# esquematico.net
KiCad netlist of a schematic drawn in EAGLE
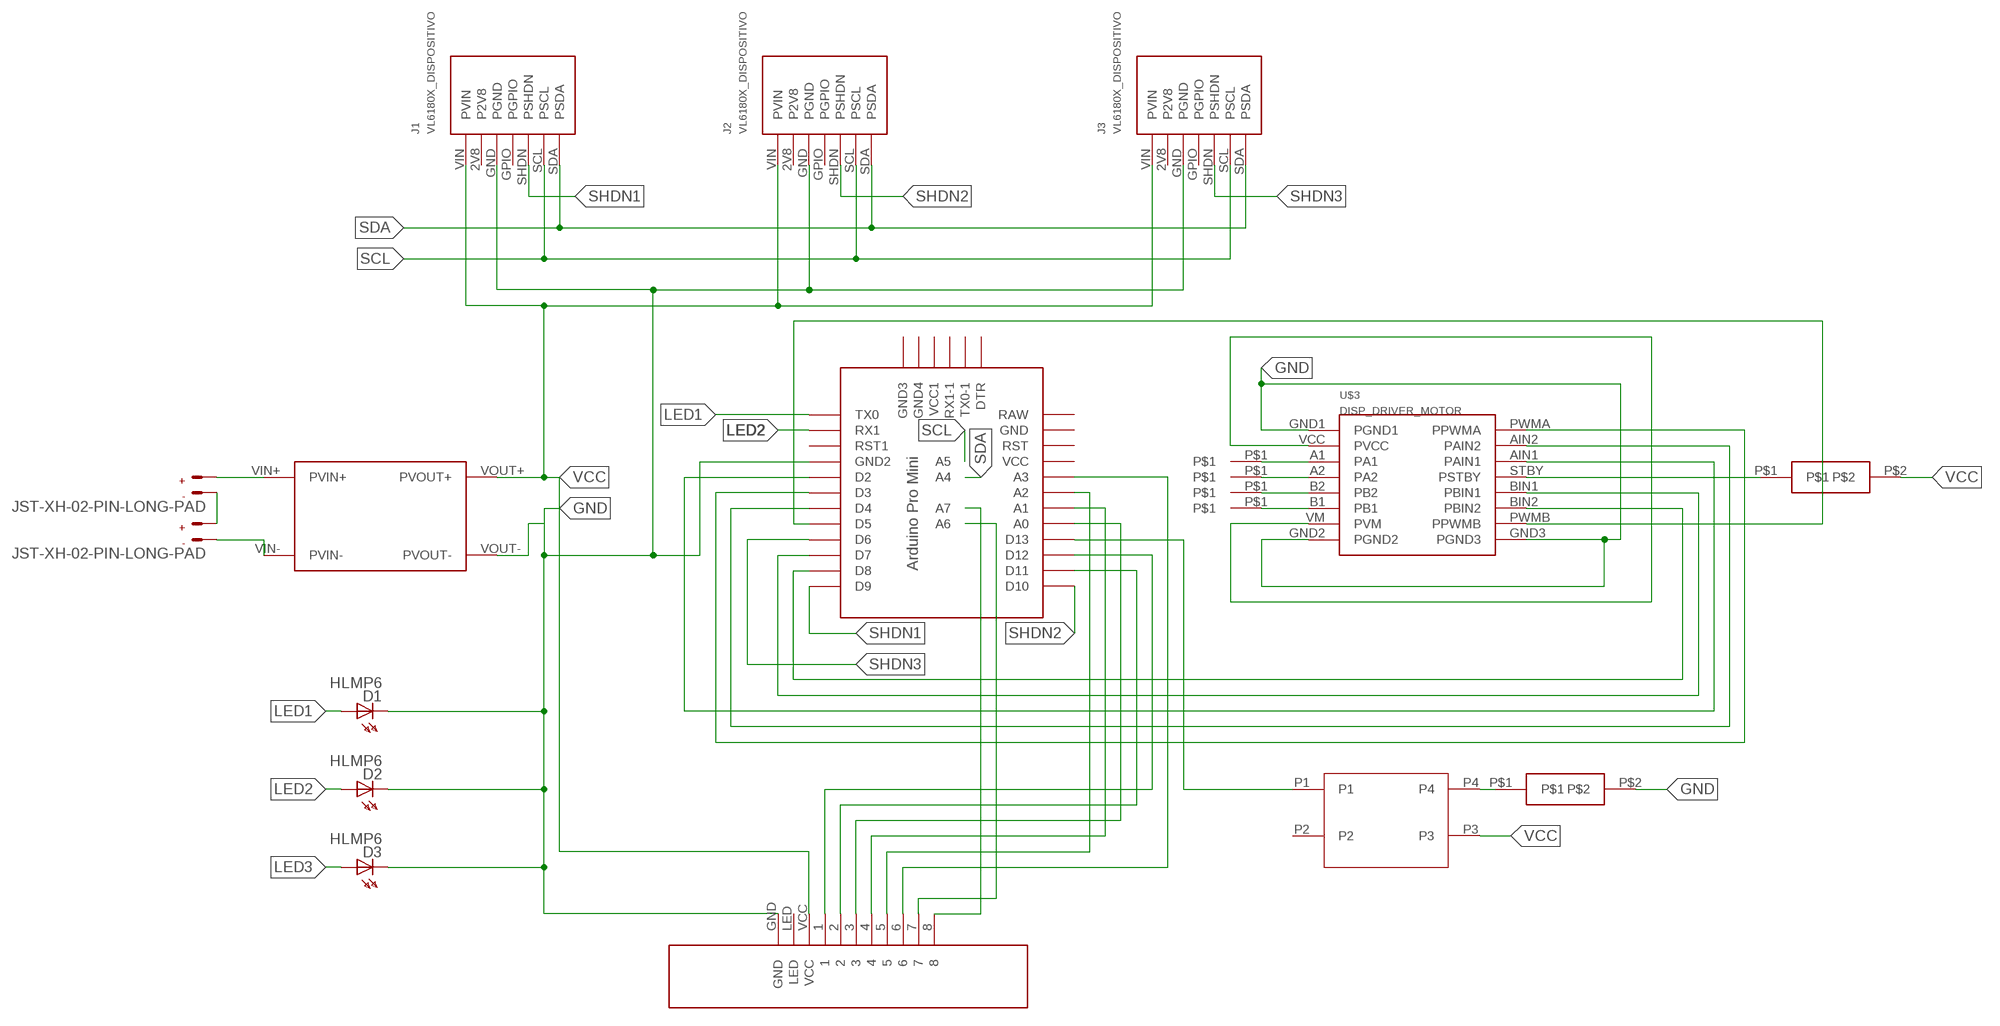
[diagram p0: schematic, sheet 1]

(export (version "E")
  (design (tool "Eeschema 10.0.6"))
  (components
    (comp (ref "D1")
      (value "HLMP6")
      (footprint "eagle-import:HLMP6")
      (fields (field (name "MF") "AGILENT TECHNOLOGIES") (field (name "MPN") "HLMP-6500"))
      (libsource (lib "eagle-import") (part "HLMP6"))
    )
    (comp (ref "D2")
      (value "HLMP6")
      (footprint "eagle-import:HLMP6")
      (fields (field (name "MF") "AGILENT TECHNOLOGIES") (field (name "MPN") "HLMP-6500"))
      (libsource (lib "eagle-import") (part "HLMP6"))
    )
    (comp (ref "D3")
      (value "HLMP6")
      (footprint "eagle-import:HLMP6")
      (fields (field (name "MF") "AGILENT TECHNOLOGIES") (field (name "MPN") "HLMP-6500"))
      (libsource (lib "eagle-import") (part "HLMP6"))
    )
    (comp (ref "DC1+")
      (value "PION_DVC")
      (footprint "eagle-import:PIN_PKG")
      (libsource (lib "eagle-import") (part "PION_DVC"))
    )
    (comp (ref "J1")
      (value "VL6180X_DISPOSITIVO")
      (footprint "eagle-import:VL6180X_PKG")
      (libsource (lib "eagle-import") (part "VL6180X_DISPOSITIVO"))
    )
    (comp (ref "J2")
      (value "VL6180X_DISPOSITIVO")
      (footprint "eagle-import:VL6180X_PKG")
      (libsource (lib "eagle-import") (part "VL6180X_DISPOSITIVO"))
    )
    (comp (ref "J3")
      (value "VL6180X_DISPOSITIVO")
      (footprint "eagle-import:VL6180X_PKG")
      (libsource (lib "eagle-import") (part "VL6180X_DISPOSITIVO"))
    )
    (comp (ref "U$1")
      (value "PRO-MINI-2")
      (footprint "eagle-import:PRO-MINI-2")
      (libsource (lib "eagle-import") (part "PRO-MINI-2"))
    )
    (comp (ref "U$2")
      (value "R_BUENO_DIPS")
      (footprint "eagle-import:R_BUENO_PKG")
      (libsource (lib "eagle-import") (part "R_BUENO_DIPS"))
    )
    (comp (ref "U$3")
      (value "DISP_DRIVER_MOTOR")
      (footprint "eagle-import:DRIVER_MOTOR")
      (libsource (lib "eagle-import") (part "DISP_DRIVER_MOTOR"))
    )
    (comp (ref "U$4")
      (value "SENSORLINEA_DISP")
      (footprint "eagle-import:SENSORLINEA_PKG")
      (libsource (lib "eagle-import") (part "SENSORLINEA_DISP"))
    )
    (comp (ref "U$5")
      (value "RES_DISP")
      (footprint "eagle-import:RES_PKG")
      (libsource (lib "eagle-import") (part "RES_DISP"))
    )
    (comp (ref "U$6")
      (value "PION_DVC")
      (footprint "eagle-import:PIN_PKG")
      (libsource (lib "eagle-import") (part "PION_DVC"))
    )
    (comp (ref "U$7")
      (value "PION_DVC")
      (footprint "eagle-import:PIN_PKG")
      (libsource (lib "eagle-import") (part "PION_DVC"))
    )
    (comp (ref "U$8")
      (value "PION_DVC")
      (footprint "eagle-import:PIN_PKG")
      (libsource (lib "eagle-import") (part "PION_DVC"))
    )
    (comp (ref "U$9")
      (value "BOTON_DEVICE")
      (footprint "eagle-import:BOTON_PACK")
      (libsource (lib "eagle-import") (part "BOTON_DEVICE"))
    )
    (comp (ref "U$10")
      (value "RES_DISP")
      (footprint "eagle-import:RES_PKG")
      (libsource (lib "eagle-import") (part "RES_DISP"))
    )
    (comp (ref "X1")
      (value "JST-XH-02-PIN-LONG-PAD")
      (footprint "eagle-import:JST-XH-02-PACKAGE-LONG-PAD")
      (libsource (lib "eagle-import") (part "JST-XH-02-PIN-LONG-PAD"))
    )
    (comp (ref "X2")
      (value "JST-XH-02-PIN-LONG-PAD")
      (footprint "eagle-import:JST-XH-02-PACKAGE-LONG-PAD")
      (libsource (lib "eagle-import") (part "JST-XH-02-PIN-LONG-PAD"))
    )
  )
  (nets
    (net (code "1") (name "GND") (class "Default")
      (node (ref "D1") (pin "K") (pinfunction "K_K") (pintype "passive"))
      (node (ref "D2") (pin "K") (pinfunction "K_K") (pintype "passive"))
      (node (ref "D3") (pin "K") (pinfunction "K_K") (pintype "passive"))
      (node (ref "J1") (pin "GND") (pinfunction "PGND_GND") (pintype "bidirectional"))
      (node (ref "J2") (pin "GND") (pinfunction "PGND_GND") (pintype "bidirectional"))
      (node (ref "J3") (pin "GND") (pinfunction "PGND_GND") (pintype "bidirectional"))
      (node (ref "U$1") (pin "GND1") (pinfunction "GND2_GND1") (pintype "bidirectional"))
      (node (ref "U$10") (pin "P$2") (pinfunction "P$2_P$2") (pintype "bidirectional"))
      (node (ref "U$2") (pin "VOUT-") (pinfunction "PVOUT-_VOUT-") (pintype "bidirectional"))
      (node (ref "U$3") (pin "GND1") (pinfunction "PGND1_GND1") (pintype "bidirectional"))
      (node (ref "U$3") (pin "GND2") (pinfunction "PGND2_GND2") (pintype "bidirectional"))
      (node (ref "U$3") (pin "GND3") (pinfunction "PGND3_GND3") (pintype "bidirectional"))
      (node (ref "U$4") (pin "GND") (pinfunction "GND_GND") (pintype "bidirectional"))
    )
    (net (code "2") (name "LED1") (class "Default")
      (node (ref "D1") (pin "A") (pinfunction "A_A") (pintype "passive"))
      (node (ref "U$1") (pin "TX0") (pinfunction "TX0_TX0") (pintype "bidirectional"))
    )
    (net (code "3") (name "LED2") (class "Default")
      (node (ref "D2") (pin "A") (pinfunction "A_A") (pintype "passive"))
      (node (ref "U$1") (pin "RX1") (pinfunction "RX1_RX1") (pintype "bidirectional"))
    )
    (net (code "4") (name "LED3") (class "Default")
      (node (ref "D3") (pin "A") (pinfunction "A_A") (pintype "passive"))
      (node (ref "U$1") (pin "D13") (pinfunction "D13_D13") (pintype "bidirectional"))
      (node (ref "U$9") (pin "P1") (pinfunction "P1_P1") (pintype "bidirectional"))
    )
    (net (code "5") (name "Net-(U$1-PadA0)") (class "Default")
      (node (ref "U$1") (pin "A0") (pinfunction "A0_A0") (pintype "bidirectional"))
      (node (ref "U$4") (pin "3") (pinfunction "3_3") (pintype "bidirectional"))
    )
    (net (code "6") (name "Net-(U$1-PadA1)") (class "Default")
      (node (ref "U$1") (pin "A1") (pinfunction "A1_A1") (pintype "bidirectional"))
      (node (ref "U$4") (pin "4") (pinfunction "4_4") (pintype "bidirectional"))
    )
    (net (code "7") (name "Net-(U$1-PadA2)") (class "Default")
      (node (ref "U$1") (pin "A2") (pinfunction "A2_A2") (pintype "bidirectional"))
      (node (ref "U$4") (pin "5") (pinfunction "5_5") (pintype "bidirectional"))
    )
    (net (code "8") (name "Net-(U$1-PadA3)") (class "Default")
      (node (ref "U$1") (pin "A3") (pinfunction "A3_A3") (pintype "bidirectional"))
      (node (ref "U$4") (pin "6") (pinfunction "6_6") (pintype "bidirectional"))
    )
    (net (code "9") (name "Net-(U$1-PadA6)") (class "Default")
      (node (ref "U$1") (pin "A6") (pinfunction "A6_A6") (pintype "bidirectional"))
      (node (ref "U$4") (pin "7") (pinfunction "7_7") (pintype "bidirectional"))
    )
    (net (code "10") (name "Net-(U$1-PadA7)") (class "Default")
      (node (ref "U$1") (pin "A7") (pinfunction "A7_A7") (pintype "bidirectional"))
      (node (ref "U$4") (pin "8") (pinfunction "8_8") (pintype "bidirectional"))
    )
    (net (code "11") (name "Net-(U$1-PadD11)") (class "Default")
      (node (ref "U$1") (pin "D11") (pinfunction "D11_D11") (pintype "bidirectional"))
      (node (ref "U$4") (pin "2") (pinfunction "2_2") (pintype "bidirectional"))
    )
    (net (code "12") (name "Net-(U$1-PadD12)") (class "Default")
      (node (ref "U$1") (pin "D12") (pinfunction "D12_D12") (pintype "bidirectional"))
      (node (ref "U$4") (pin "1") (pinfunction "1_1") (pintype "bidirectional"))
    )
    (net (code "13") (name "Net-(U$2-PVIN+)") (class "Default")
      (node (ref "U$2") (pin "VIN+") (pinfunction "PVIN+_VIN+") (pintype "bidirectional"))
      (node (ref "X1") (pin "2") (pinfunction "S_2") (pintype "passive"))
    )
    (net (code "14") (name "Net-(U$2-PVIN-)") (class "Default")
      (node (ref "U$2") (pin "VIN-") (pinfunction "PVIN-_VIN-") (pintype "bidirectional"))
      (node (ref "X2") (pin "1") (pinfunction "S_1") (pintype "passive"))
    )
    (net (code "15") (name "Net-(U$3-PA1)") (class "Default")
      (node (ref "DC1+") (pin "P$1") (pinfunction "P$1_P$1") (pintype "bidirectional"))
      (node (ref "U$3") (pin "A1") (pinfunction "PA1_A1") (pintype "bidirectional"))
    )
    (net (code "16") (name "Net-(U$3-PA2)") (class "Default")
      (node (ref "U$3") (pin "A2") (pinfunction "PA2_A2") (pintype "bidirectional"))
      (node (ref "U$6") (pin "P$1") (pinfunction "P$1_P$1") (pintype "bidirectional"))
    )
    (net (code "17") (name "Net-(U$3-PAIN1)") (class "Default")
      (node (ref "U$1") (pin "D2") (pinfunction "D2_D2") (pintype "bidirectional"))
      (node (ref "U$3") (pin "AIN1") (pinfunction "PAIN1_AIN1") (pintype "bidirectional"))
    )
    (net (code "18") (name "Net-(U$3-PAIN2)") (class "Default")
      (node (ref "U$1") (pin "D4") (pinfunction "D4_D4") (pintype "bidirectional"))
      (node (ref "U$3") (pin "AIN2") (pinfunction "PAIN2_AIN2") (pintype "bidirectional"))
    )
    (net (code "19") (name "Net-(U$3-PB1)") (class "Default")
      (node (ref "U$3") (pin "B1") (pinfunction "PB1_B1") (pintype "bidirectional"))
      (node (ref "U$8") (pin "P$1") (pinfunction "P$1_P$1") (pintype "bidirectional"))
    )
    (net (code "20") (name "Net-(U$3-PB2)") (class "Default")
      (node (ref "U$3") (pin "B2") (pinfunction "PB2_B2") (pintype "bidirectional"))
      (node (ref "U$7") (pin "P$1") (pinfunction "P$1_P$1") (pintype "bidirectional"))
    )
    (net (code "21") (name "Net-(U$3-PBIN1)") (class "Default")
      (node (ref "U$1") (pin "D7") (pinfunction "D7_D7") (pintype "bidirectional"))
      (node (ref "U$3") (pin "BIN1") (pinfunction "PBIN1_BIN1") (pintype "bidirectional"))
    )
    (net (code "22") (name "Net-(U$3-PBIN2)") (class "Default")
      (node (ref "U$1") (pin "D8") (pinfunction "D8_D8") (pintype "bidirectional"))
      (node (ref "U$3") (pin "BIN2") (pinfunction "PBIN2_BIN2") (pintype "bidirectional"))
    )
    (net (code "23") (name "Net-(U$3-PPWMA)") (class "Default")
      (node (ref "U$1") (pin "D3") (pinfunction "D3_D3") (pintype "bidirectional"))
      (node (ref "U$3") (pin "PWMA") (pinfunction "PPWMA_PWMA") (pintype "bidirectional"))
    )
    (net (code "24") (name "Net-(U$3-PPWMB)") (class "Default")
      (node (ref "U$1") (pin "D5") (pinfunction "D5_D5") (pintype "bidirectional"))
      (node (ref "U$3") (pin "PWMB") (pinfunction "PPWMB_PWMB") (pintype "bidirectional"))
    )
    (net (code "25") (name "Net-(U$3-PSTBY)") (class "Default")
      (node (ref "U$3") (pin "STBY") (pinfunction "PSTBY_STBY") (pintype "bidirectional"))
      (node (ref "U$5") (pin "P$1") (pinfunction "P$1_P$1") (pintype "bidirectional"))
    )
    (net (code "26") (name "Net-(U$10-PadP$1)") (class "Default")
      (node (ref "U$10") (pin "P$1") (pinfunction "P$1_P$1") (pintype "bidirectional"))
      (node (ref "U$9") (pin "P4") (pinfunction "P4_P4") (pintype "bidirectional"))
    )
    (net (code "27") (name "Net-(X1A-S)") (class "Default")
      (node (ref "X1") (pin "1") (pinfunction "S_1") (pintype "passive"))
      (node (ref "X2") (pin "2") (pinfunction "S_2") (pintype "passive"))
    )
    (net (code "28") (name "SCL") (class "Default")
      (node (ref "J1") (pin "SCL") (pinfunction "PSCL_SCL") (pintype "bidirectional"))
      (node (ref "J2") (pin "SCL") (pinfunction "PSCL_SCL") (pintype "bidirectional"))
      (node (ref "J3") (pin "SCL") (pinfunction "PSCL_SCL") (pintype "bidirectional"))
      (node (ref "U$1") (pin "A5") (pinfunction "A5_A5") (pintype "bidirectional"))
    )
    (net (code "29") (name "SDA") (class "Default")
      (node (ref "J1") (pin "SDA") (pinfunction "PSDA_SDA") (pintype "bidirectional"))
      (node (ref "J2") (pin "SDA") (pinfunction "PSDA_SDA") (pintype "bidirectional"))
      (node (ref "J3") (pin "SDA") (pinfunction "PSDA_SDA") (pintype "bidirectional"))
      (node (ref "U$1") (pin "A4") (pinfunction "A4_A4") (pintype "bidirectional"))
    )
    (net (code "30") (name "SHDN1") (class "Default")
      (node (ref "J1") (pin "SHDN") (pinfunction "PSHDN_SHDN") (pintype "bidirectional"))
      (node (ref "U$1") (pin "D9") (pinfunction "D9_D9") (pintype "bidirectional"))
    )
    (net (code "31") (name "SHDN2") (class "Default")
      (node (ref "J2") (pin "SHDN") (pinfunction "PSHDN_SHDN") (pintype "bidirectional"))
      (node (ref "U$1") (pin "D10") (pinfunction "D10_D10") (pintype "bidirectional"))
    )
    (net (code "32") (name "SHDN3") (class "Default")
      (node (ref "J3") (pin "SHDN") (pinfunction "PSHDN_SHDN") (pintype "bidirectional"))
      (node (ref "U$1") (pin "D6") (pinfunction "D6_D6") (pintype "bidirectional"))
    )
    (net (code "33") (name "VCC") (class "Default")
      (node (ref "J1") (pin "VIN") (pinfunction "PVIN_VIN") (pintype "bidirectional"))
      (node (ref "J2") (pin "VIN") (pinfunction "PVIN_VIN") (pintype "bidirectional"))
      (node (ref "J3") (pin "VIN") (pinfunction "PVIN_VIN") (pintype "bidirectional"))
      (node (ref "U$2") (pin "VOUT+") (pinfunction "PVOUT+_VOUT+") (pintype "bidirectional"))
      (node (ref "U$3") (pin "VCC") (pinfunction "PVCC_VCC") (pintype "bidirectional"))
      (node (ref "U$3") (pin "VM") (pinfunction "PVM_VM") (pintype "bidirectional"))
      (node (ref "U$4") (pin "VCC") (pinfunction "VCC_VCC") (pintype "bidirectional"))
      (node (ref "U$5") (pin "P$2") (pinfunction "P$2_P$2") (pintype "bidirectional"))
      (node (ref "U$9") (pin "P3") (pinfunction "P3_P3") (pintype "bidirectional"))
    )
    (net (code "34") (name "unconnected-(J1-P2V8-Pad2V8)") (class "Default")
      (node (ref "J1") (pin "2V8") (pinfunction "P2V8_2V8") (pintype "bidirectional"))
    )
    (net (code "35") (name "unconnected-(J1-PGPIO-PadGPIO)") (class "Default")
      (node (ref "J1") (pin "GPIO") (pinfunction "PGPIO_GPIO") (pintype "bidirectional"))
    )
    (net (code "36") (name "unconnected-(J2-P2V8-Pad2V8)") (class "Default")
      (node (ref "J2") (pin "2V8") (pinfunction "P2V8_2V8") (pintype "bidirectional"))
    )
    (net (code "37") (name "unconnected-(J2-PGPIO-PadGPIO)") (class "Default")
      (node (ref "J2") (pin "GPIO") (pinfunction "PGPIO_GPIO") (pintype "bidirectional"))
    )
    (net (code "38") (name "unconnected-(J3-P2V8-Pad2V8)") (class "Default")
      (node (ref "J3") (pin "2V8") (pinfunction "P2V8_2V8") (pintype "bidirectional"))
    )
    (net (code "39") (name "unconnected-(J3-PGPIO-PadGPIO)") (class "Default")
      (node (ref "J3") (pin "GPIO") (pinfunction "PGPIO_GPIO") (pintype "bidirectional"))
    )
    (net (code "40") (name "unconnected-(U$1-GND3-PadGND2)") (class "Default")
      (node (ref "U$1") (pin "GND2") (pinfunction "GND3_GND2") (pintype "bidirectional"))
    )
    (net (code "41") (name "unconnected-(U$1-GND4-PadGND3)") (class "Default")
      (node (ref "U$1") (pin "GND3") (pinfunction "GND4_GND3") (pintype "bidirectional"))
    )
    (net (code "42") (name "unconnected-(U$1-PadDTR)") (class "Default")
      (node (ref "U$1") (pin "DTR") (pinfunction "DTR_DTR") (pintype "bidirectional"))
    )
    (net (code "43") (name "unconnected-(U$1-PadGND)") (class "Default")
      (node (ref "U$1") (pin "GND") (pinfunction "GND_GND") (pintype "bidirectional"))
    )
    (net (code "44") (name "unconnected-(U$1-PadRAW)") (class "Default")
      (node (ref "U$1") (pin "RAW") (pinfunction "RAW_RAW") (pintype "bidirectional"))
    )
    (net (code "45") (name "unconnected-(U$1-PadRST)") (class "Default")
      (node (ref "U$1") (pin "RST") (pinfunction "RST_RST") (pintype "bidirectional"))
    )
    (net (code "46") (name "unconnected-(U$1-PadRST1)") (class "Default")
      (node (ref "U$1") (pin "RST1") (pinfunction "RST1_RST1") (pintype "bidirectional"))
    )
    (net (code "47") (name "unconnected-(U$1-PadRX1-1)") (class "Default")
      (node (ref "U$1") (pin "RX1-1") (pinfunction "RX1-1_RX1-1") (pintype "bidirectional"))
    )
    (net (code "48") (name "unconnected-(U$1-PadTX0-1)") (class "Default")
      (node (ref "U$1") (pin "TX0-1") (pinfunction "TX0-1_TX0-1") (pintype "bidirectional"))
    )
    (net (code "49") (name "unconnected-(U$1-PadVCC)") (class "Default")
      (node (ref "U$1") (pin "VCC") (pinfunction "VCC_VCC") (pintype "bidirectional"))
    )
    (net (code "50") (name "unconnected-(U$1-PadVCC1)") (class "Default")
      (node (ref "U$1") (pin "VCC1") (pinfunction "VCC1_VCC1") (pintype "bidirectional"))
    )
    (net (code "51") (name "unconnected-(U$4-PadLED)") (class "Default")
      (node (ref "U$4") (pin "LED") (pinfunction "LED_LED") (pintype "bidirectional"))
    )
    (net (code "52") (name "unconnected-(U$9-PadP2)") (class "Default")
      (node (ref "U$9") (pin "P2") (pinfunction "P2_P2") (pintype "bidirectional"))
    )
  )
)
